# M_J_ext_e_ink_disp.net
KiCad netlist of a schematic drawn in EAGLE
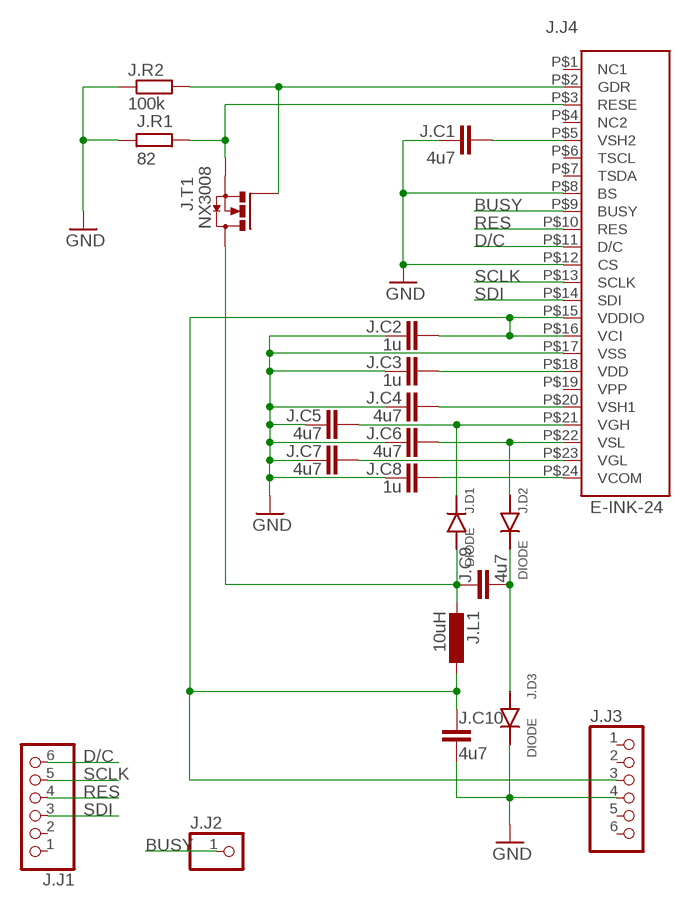
[diagram p0: schematic, sheet 1]

(export (version "E")
  (design (tool "Eeschema 10.0.6"))
  (components
    (comp (ref "J.C1")
      (value "4u7")
      (footprint "eagle-import:C0603")
      (libsource (lib "eagle-import") (part "C-EUC0603"))
    )
    (comp (ref "J.C2")
      (value "1u")
      (footprint "eagle-import:C0603")
      (libsource (lib "eagle-import") (part "C-EUC0603"))
    )
    (comp (ref "J.C3")
      (value "1u")
      (footprint "eagle-import:C0603")
      (libsource (lib "eagle-import") (part "C-EUC0603"))
    )
    (comp (ref "J.C4")
      (value "4u7")
      (footprint "eagle-import:C0603")
      (libsource (lib "eagle-import") (part "C-EUC0603"))
    )
    (comp (ref "J.C5")
      (value "4u7")
      (footprint "eagle-import:C0603")
      (libsource (lib "eagle-import") (part "C-EUC0603"))
    )
    (comp (ref "J.C6")
      (value "4u7")
      (footprint "eagle-import:C0603")
      (libsource (lib "eagle-import") (part "C-EUC0603"))
    )
    (comp (ref "J.C7")
      (value "4u7")
      (footprint "eagle-import:C0603")
      (libsource (lib "eagle-import") (part "C-EUC0603"))
    )
    (comp (ref "J.C8")
      (value "1u")
      (footprint "eagle-import:C0603")
      (libsource (lib "eagle-import") (part "C-EUC0603"))
    )
    (comp (ref "J.C9")
      (value "4u7")
      (footprint "eagle-import:C0603")
      (libsource (lib "eagle-import") (part "C-EUC0603"))
    )
    (comp (ref "J.C10")
      (value "4u7")
      (footprint "eagle-import:C0603")
      (libsource (lib "eagle-import") (part "C-EUC0603"))
    )
    (comp (ref "J.D1")
      (value "DIODE")
      (footprint "eagle-import:DIODE")
      (libsource (lib "eagle-import") (part "DIODE"))
    )
    (comp (ref "J.D2")
      (value "DIODE")
      (footprint "eagle-import:DIODE")
      (libsource (lib "eagle-import") (part "DIODE"))
    )
    (comp (ref "J.D3")
      (value "DIODE")
      (footprint "eagle-import:DIODE")
      (libsource (lib "eagle-import") (part "DIODE"))
    )
    (comp (ref "J.J1")
      (value "PINHD-1X6")
      (footprint "eagle-import:1X06")
      (libsource (lib "eagle-import") (part "PINHD-1X6"))
    )
    (comp (ref "J.J2")
      (value "PINHD-1X1")
      (footprint "eagle-import:1X01")
      (libsource (lib "eagle-import") (part "PINHD-1X1"))
    )
    (comp (ref "J.J3")
      (value "PINHD-1X6")
      (footprint "eagle-import:1X06")
      (libsource (lib "eagle-import") (part "PINHD-1X6"))
    )
    (comp (ref "J.J4")
      (value "E-INK-24")
      (footprint "eagle-import:E-INK-24")
      (libsource (lib "eagle-import") (part "E-INK-24"))
    )
    (comp (ref "J.L1")
      (value "10uH")
      (footprint "eagle-import:L3230M")
      (libsource (lib "eagle-import") (part "L-EUL3230M"))
    )
    (comp (ref "J.R1")
      (value "82")
      (footprint "eagle-import:R0603")
      (libsource (lib "eagle-import") (part "resistor_R-EU_R0603"))
    )
    (comp (ref "J.R2")
      (value "100k")
      (footprint "eagle-import:R0603")
      (libsource (lib "eagle-import") (part "R-EU_R0603"))
    )
    (comp (ref "J.T1")
      (value "NX3008")
      (footprint "eagle-import:SO23")
      (libsource (lib "eagle-import") (part "N-MOSFET"))
    )
  )
  (nets
    (net (code "1") (name "/BUSY") (class "Default")
      (node (ref "J.J2") (pin "1") (pinfunction "1_1") (pintype "passive"))
      (node (ref "J.J4") (pin "P$9") (pinfunction "BUSY_P$9") (pintype "bidirectional"))
    )
    (net (code "2") (name "/D{slash}C") (class "Default")
      (node (ref "J.J1") (pin "6") (pinfunction "6_6") (pintype "passive"))
      (node (ref "J.J4") (pin "P$11") (pinfunction "D/C_P$11") (pintype "bidirectional"))
    )
    (net (code "3") (name "/RES") (class "Default")
      (node (ref "J.J1") (pin "4") (pinfunction "4_4") (pintype "passive"))
      (node (ref "J.J4") (pin "P$10") (pinfunction "RES_P$10") (pintype "bidirectional"))
    )
    (net (code "4") (name "/SCLK") (class "Default")
      (node (ref "J.J1") (pin "5") (pinfunction "5_5") (pintype "passive"))
      (node (ref "J.J4") (pin "P$13") (pinfunction "SCLK_P$13") (pintype "bidirectional"))
    )
    (net (code "5") (name "/SDI") (class "Default")
      (node (ref "J.J1") (pin "3") (pinfunction "3_3") (pintype "passive"))
      (node (ref "J.J4") (pin "P$14") (pinfunction "SDI_P$14") (pintype "bidirectional"))
    )
    (net (code "6") (name "GND") (class "Default")
      (node (ref "J.C1") (pin "2") (pinfunction "2_2") (pintype "passive"))
      (node (ref "J.C10") (pin "2") (pinfunction "2_2") (pintype "passive"))
      (node (ref "J.C2") (pin "2") (pinfunction "2_2") (pintype "passive"))
      (node (ref "J.C3") (pin "2") (pinfunction "2_2") (pintype "passive"))
      (node (ref "J.C4") (pin "2") (pinfunction "2_2") (pintype "passive"))
      (node (ref "J.C5") (pin "2") (pinfunction "2_2") (pintype "passive"))
      (node (ref "J.C6") (pin "2") (pinfunction "2_2") (pintype "passive"))
      (node (ref "J.C7") (pin "2") (pinfunction "2_2") (pintype "passive"))
      (node (ref "J.C8") (pin "2") (pinfunction "2_2") (pintype "passive"))
      (node (ref "J.D3") (pin "C") (pinfunction "C_C") (pintype "bidirectional"))
      (node (ref "J.J3") (pin "4") (pinfunction "4_4") (pintype "passive"))
      (node (ref "J.J4") (pin "P$12") (pinfunction "CS_P$12") (pintype "bidirectional"))
      (node (ref "J.J4") (pin "P$17") (pinfunction "VSS_P$17") (pintype "bidirectional"))
      (node (ref "J.J4") (pin "P$8") (pinfunction "BS_P$8") (pintype "bidirectional"))
      (node (ref "J.R1") (pin "2") (pinfunction "2_2") (pintype "passive"))
      (node (ref "J.R2") (pin "1") (pinfunction "1_1") (pintype "passive"))
    )
    (net (code "7") (name "Net-(J.C9-Pad1)") (class "Default")
      (node (ref "J.C9") (pin "1") (pinfunction "1_1") (pintype "passive"))
      (node (ref "J.D1") (pin "A") (pinfunction "A_A") (pintype "bidirectional"))
      (node (ref "J.L1") (pin "2") (pinfunction "2_2") (pintype "passive"))
      (node (ref "J.T1") (pin "D") (pinfunction "D_D") (pintype "passive"))
    )
    (net (code "8") (name "Net-(J.C9-Pad2)") (class "Default")
      (node (ref "J.C9") (pin "2") (pinfunction "2_2") (pintype "passive"))
      (node (ref "J.D2") (pin "C") (pinfunction "C_C") (pintype "bidirectional"))
      (node (ref "J.D3") (pin "A") (pinfunction "A_A") (pintype "bidirectional"))
    )
    (net (code "9") (name "Net-(J.J4-GDR)") (class "Default")
      (node (ref "J.J4") (pin "P$2") (pinfunction "GDR_P$2") (pintype "bidirectional"))
      (node (ref "J.R2") (pin "2") (pinfunction "2_2") (pintype "passive"))
      (node (ref "J.T1") (pin "G") (pinfunction "G_G") (pintype "passive"))
    )
    (net (code "10") (name "Net-(J.J4-RESE)") (class "Default")
      (node (ref "J.J4") (pin "P$3") (pinfunction "RESE_P$3") (pintype "bidirectional"))
      (node (ref "J.R1") (pin "1") (pinfunction "1_1") (pintype "passive"))
      (node (ref "J.T1") (pin "S") (pinfunction "S_S") (pintype "passive"))
    )
    (net (code "11") (name "Net-(J.J4-VCI)") (class "Default")
      (node (ref "J.C10") (pin "1") (pinfunction "1_1") (pintype "passive"))
      (node (ref "J.C2") (pin "1") (pinfunction "1_1") (pintype "passive"))
      (node (ref "J.J3") (pin "3") (pinfunction "3_3") (pintype "passive"))
      (node (ref "J.J4") (pin "P$15") (pinfunction "VDDIO_P$15") (pintype "bidirectional"))
      (node (ref "J.J4") (pin "P$16") (pinfunction "VCI_P$16") (pintype "bidirectional"))
      (node (ref "J.L1") (pin "1") (pinfunction "1_1") (pintype "passive"))
    )
    (net (code "12") (name "Net-(J.J4-VCOM)") (class "Default")
      (node (ref "J.C8") (pin "1") (pinfunction "1_1") (pintype "passive"))
      (node (ref "J.J4") (pin "P$24") (pinfunction "VCOM_P$24") (pintype "bidirectional"))
    )
    (net (code "13") (name "Net-(J.J4-VDD)") (class "Default")
      (node (ref "J.C3") (pin "1") (pinfunction "1_1") (pintype "passive"))
      (node (ref "J.J4") (pin "P$18") (pinfunction "VDD_P$18") (pintype "bidirectional"))
    )
    (net (code "14") (name "Net-(J.J4-VGH)") (class "Default")
      (node (ref "J.C5") (pin "1") (pinfunction "1_1") (pintype "passive"))
      (node (ref "J.D1") (pin "C") (pinfunction "C_C") (pintype "bidirectional"))
      (node (ref "J.J4") (pin "P$21") (pinfunction "VGH_P$21") (pintype "bidirectional"))
    )
    (net (code "15") (name "Net-(J.J4-VGL)") (class "Default")
      (node (ref "J.C7") (pin "1") (pinfunction "1_1") (pintype "passive"))
      (node (ref "J.J4") (pin "P$23") (pinfunction "VGL_P$23") (pintype "bidirectional"))
    )
    (net (code "16") (name "Net-(J.J4-VSH1)") (class "Default")
      (node (ref "J.C4") (pin "1") (pinfunction "1_1") (pintype "passive"))
      (node (ref "J.J4") (pin "P$20") (pinfunction "VSH1_P$20") (pintype "bidirectional"))
    )
    (net (code "17") (name "Net-(J.J4-VSH2)") (class "Default")
      (node (ref "J.C1") (pin "1") (pinfunction "1_1") (pintype "passive"))
      (node (ref "J.J4") (pin "P$5") (pinfunction "VSH2_P$5") (pintype "bidirectional"))
    )
    (net (code "18") (name "Net-(J.J4-VSL)") (class "Default")
      (node (ref "J.C6") (pin "1") (pinfunction "1_1") (pintype "passive"))
      (node (ref "J.D2") (pin "A") (pinfunction "A_A") (pintype "bidirectional"))
      (node (ref "J.J4") (pin "P$22") (pinfunction "VSL_P$22") (pintype "bidirectional"))
    )
    (net (code "19") (name "unconnected-(J.J1-Pad1)") (class "Default")
      (node (ref "J.J1") (pin "1") (pinfunction "1_1") (pintype "passive"))
    )
    (net (code "20") (name "unconnected-(J.J1-Pad2)") (class "Default")
      (node (ref "J.J1") (pin "2") (pinfunction "2_2") (pintype "passive"))
    )
    (net (code "21") (name "unconnected-(J.J3-Pad1)") (class "Default")
      (node (ref "J.J3") (pin "1") (pinfunction "1_1") (pintype "passive"))
    )
    (net (code "22") (name "unconnected-(J.J3-Pad2)") (class "Default")
      (node (ref "J.J3") (pin "2") (pinfunction "2_2") (pintype "passive"))
    )
    (net (code "23") (name "unconnected-(J.J3-Pad5)") (class "Default")
      (node (ref "J.J3") (pin "5") (pinfunction "5_5") (pintype "passive"))
    )
    (net (code "24") (name "unconnected-(J.J3-Pad6)") (class "Default")
      (node (ref "J.J3") (pin "6") (pinfunction "6_6") (pintype "passive"))
    )
    (net (code "25") (name "unconnected-(J.J4-NC1-PadP$1)") (class "Default")
      (node (ref "J.J4") (pin "P$1") (pinfunction "NC1_P$1") (pintype "bidirectional"))
    )
    (net (code "26") (name "unconnected-(J.J4-NC2-PadP$4)") (class "Default")
      (node (ref "J.J4") (pin "P$4") (pinfunction "NC2_P$4") (pintype "bidirectional"))
    )
    (net (code "27") (name "unconnected-(J.J4-TSCL-PadP$6)") (class "Default")
      (node (ref "J.J4") (pin "P$6") (pinfunction "TSCL_P$6") (pintype "bidirectional"))
    )
    (net (code "28") (name "unconnected-(J.J4-TSDA-PadP$7)") (class "Default")
      (node (ref "J.J4") (pin "P$7") (pinfunction "TSDA_P$7") (pintype "bidirectional"))
    )
    (net (code "29") (name "unconnected-(J.J4-VPP-PadP$19)") (class "Default")
      (node (ref "J.J4") (pin "P$19") (pinfunction "VPP_P$19") (pintype "bidirectional"))
    )
  )
)
